# buckboost.net
KiCad netlist of a schematic drawn in EAGLE
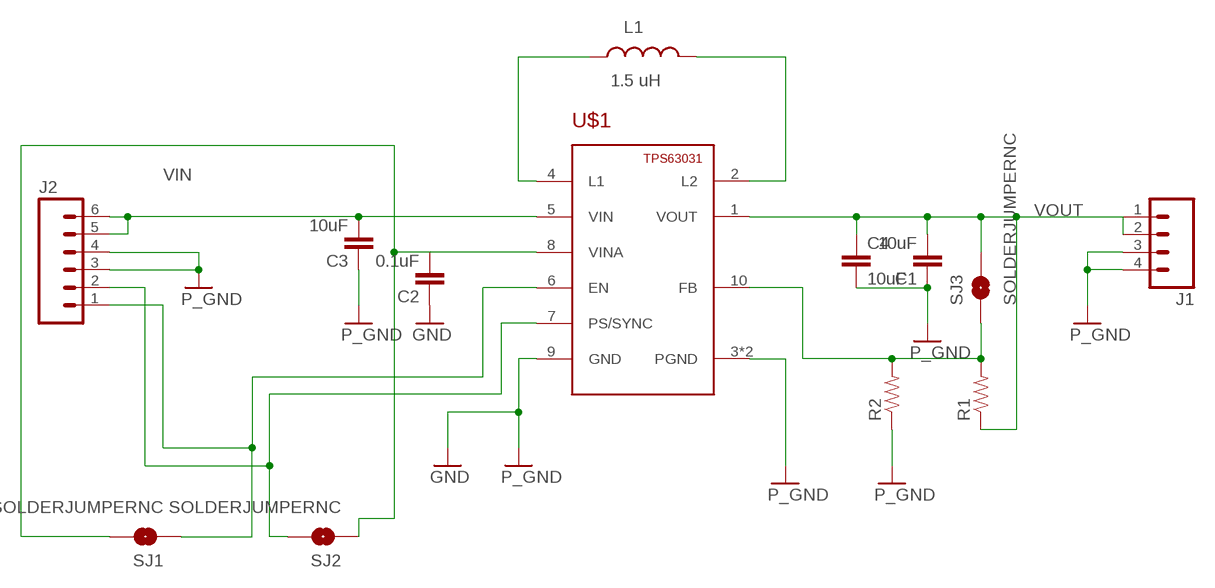
[diagram p0: schematic, sheet 1]

(export (version "E")
  (design (tool "Eeschema 10.0.6"))
  (components
    (comp (ref "C1")
      (value "10uF")
      (footprint "eagle-import:1206")
      (libsource (lib "eagle-import") (part "CAP1206"))
    )
    (comp (ref "C2")
      (value "0.1uF")
      (footprint "eagle-import:1206")
      (libsource (lib "eagle-import") (part "CAP1206"))
    )
    (comp (ref "C3")
      (value "10uF")
      (footprint "eagle-import:1206")
      (libsource (lib "eagle-import") (part "CAP1206"))
    )
    (comp (ref "C4")
      (value "10uF")
      (footprint "eagle-import:1206")
      (libsource (lib "eagle-import") (part "CAP1206"))
    )
    (comp (ref "J1")
      (value "M04PTH")
      (footprint "eagle-import:1X04")
      (libsource (lib "eagle-import") (part "M04PTH"))
    )
    (comp (ref "J2")
      (value "M06SILK_FEMALE_PTH")
      (footprint "eagle-import:1X06")
      (libsource (lib "eagle-import") (part "M06SILK_FEMALE_PTH"))
    )
    (comp (ref "L1")
      (value "1.5 uH")
      (footprint "eagle-import:IND1212")
      (libsource (lib "eagle-import") (part "INDUCTOR"))
    )
    (comp (ref "R1")
      (value "RESISTOR1206")
      (footprint "eagle-import:1206")
      (libsource (lib "eagle-import") (part "RESISTOR1206"))
    )
    (comp (ref "R2")
      (value "RESISTOR1206")
      (footprint "eagle-import:1206")
      (libsource (lib "eagle-import") (part "RESISTOR1206"))
    )
    (comp (ref "SJ1")
      (value "SOLDERJUMPERNC")
      (footprint "eagle-import:SJ_2S")
      (libsource (lib "eagle-import") (part "SOLDERJUMPERNC"))
    )
    (comp (ref "SJ2")
      (value "SOLDERJUMPERNC")
      (footprint "eagle-import:SJ_2S")
      (libsource (lib "eagle-import") (part "SOLDERJUMPERNC"))
    )
    (comp (ref "SJ3")
      (value "SOLDERJUMPERNC")
      (footprint "eagle-import:SJ_2S")
      (libsource (lib "eagle-import") (part "SOLDERJUMPERNC"))
    )
    (comp (ref "U$1")
      (value "TPS63031")
      (footprint "eagle-import:SON-10")
      (libsource (lib "eagle-import") (part "TPS63031"))
    )
  )
  (nets
    (net (code "1") (name "/VIN") (class "Default")
      (node (ref "C3") (pin "2") (pinfunction "2_2") (pintype "passive"))
      (node (ref "J2") (pin "5") (pinfunction "5_5") (pintype "passive"))
      (node (ref "J2") (pin "6") (pinfunction "6_6") (pintype "passive"))
      (node (ref "U$1") (pin "5") (pinfunction "VIN_5") (pintype "bidirectional"))
    )
    (net (code "2") (name "/VOUT") (class "Default")
      (node (ref "C1") (pin "2") (pinfunction "2_2") (pintype "passive"))
      (node (ref "C4") (pin "1") (pinfunction "1_1") (pintype "passive"))
      (node (ref "J1") (pin "1") (pinfunction "1_1") (pintype "passive"))
      (node (ref "J1") (pin "2") (pinfunction "2_2") (pintype "passive"))
      (node (ref "R1") (pin "1") (pinfunction "1_1") (pintype "passive"))
      (node (ref "SJ3") (pin "2") (pinfunction "2_2") (pintype "passive"))
      (node (ref "U$1") (pin "1") (pinfunction "VOUT_1") (pintype "bidirectional"))
    )
    (net (code "3") (name "GND") (class "Default")
      (node (ref "C1") (pin "1") (pinfunction "1_1") (pintype "passive"))
      (node (ref "C2") (pin "1") (pinfunction "1_1") (pintype "passive"))
      (node (ref "C3") (pin "1") (pinfunction "1_1") (pintype "passive"))
      (node (ref "C4") (pin "2") (pinfunction "2_2") (pintype "passive"))
      (node (ref "J1") (pin "3") (pinfunction "3_3") (pintype "passive"))
      (node (ref "J1") (pin "4") (pinfunction "4_4") (pintype "passive"))
      (node (ref "J2") (pin "3") (pinfunction "3_3") (pintype "passive"))
      (node (ref "J2") (pin "4") (pinfunction "4_4") (pintype "passive"))
      (node (ref "R2") (pin "1") (pinfunction "1_1") (pintype "passive"))
      (node (ref "U$1") (pin "3") (pinfunction "PGND_3") (pintype "bidirectional"))
      (node (ref "U$1") (pin "9") (pinfunction "GND_9") (pintype "bidirectional"))
      (node (ref "U$1") (pin "PAD") (pinfunction "PGND_PAD") (pintype "bidirectional"))
    )
    (net (code "4") (name "Net-(L1-1)") (class "Default")
      (node (ref "L1") (pin "P$1") (pinfunction "1_P$1") (pintype "passive"))
      (node (ref "U$1") (pin "4") (pinfunction "L1_4") (pintype "bidirectional"))
    )
    (net (code "5") (name "Net-(L1-2)") (class "Default")
      (node (ref "L1") (pin "P$2") (pinfunction "2_P$2") (pintype "passive"))
      (node (ref "U$1") (pin "2") (pinfunction "L2_2") (pintype "bidirectional"))
    )
    (net (code "6") (name "Net-(U$1-EN)") (class "Default")
      (node (ref "J2") (pin "1") (pinfunction "1_1") (pintype "passive"))
      (node (ref "SJ1") (pin "1") (pinfunction "1_1") (pintype "passive"))
      (node (ref "U$1") (pin "6") (pinfunction "EN_6") (pintype "bidirectional"))
    )
    (net (code "7") (name "Net-(U$1-FB)") (class "Default")
      (node (ref "R1") (pin "2") (pinfunction "2_2") (pintype "passive"))
      (node (ref "R2") (pin "2") (pinfunction "2_2") (pintype "passive"))
      (node (ref "SJ3") (pin "1") (pinfunction "1_1") (pintype "passive"))
      (node (ref "U$1") (pin "10") (pinfunction "FB_10") (pintype "bidirectional"))
    )
    (net (code "8") (name "Net-(U$1-PS{slash}SYNC)") (class "Default")
      (node (ref "J2") (pin "2") (pinfunction "2_2") (pintype "passive"))
      (node (ref "SJ2") (pin "2") (pinfunction "2_2") (pintype "passive"))
      (node (ref "U$1") (pin "7") (pinfunction "PS/SYNC_7") (pintype "bidirectional"))
    )
    (net (code "9") (name "Net-(U$1-VINA)") (class "Default")
      (node (ref "C2") (pin "2") (pinfunction "2_2") (pintype "passive"))
      (node (ref "SJ1") (pin "2") (pinfunction "2_2") (pintype "passive"))
      (node (ref "SJ2") (pin "1") (pinfunction "1_1") (pintype "passive"))
      (node (ref "U$1") (pin "8") (pinfunction "VINA_8") (pintype "bidirectional"))
    )
  )
)
